# PGA.net
KiCad netlist of a schematic drawn in Altium Designer
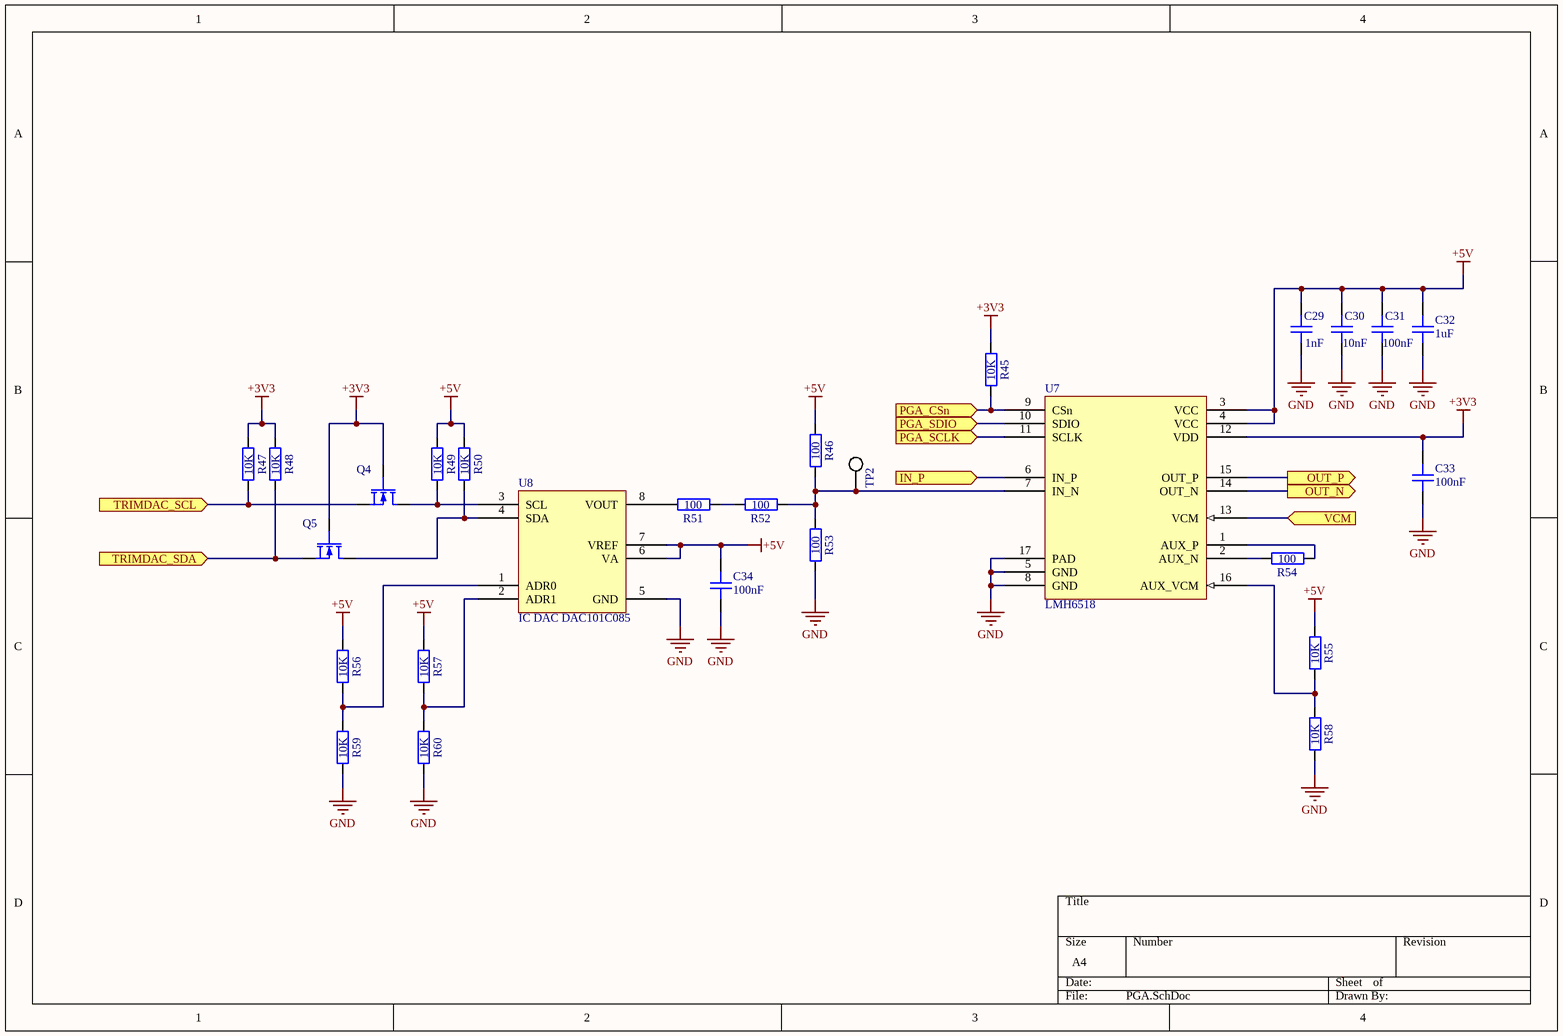
[diagram p0: PGA.SchDoc]

(export (version "E")
  (design (tool "Eeschema 10.0.6"))
  (components
    (comp (ref "C29")
      (value "1nF")
      (footprint "GEN_C_0402")
      (fields (field (name "Comment") "CAP 1nF 50V X7R 0402"))
      (libsource (lib "DSO") (part "CAP 1nF 50V X7R 0402"))
    )
    (comp (ref "C30")
      (value "10nF")
      (footprint "GEN_C_0402")
      (fields (field (name "Comment") "CAP 10nF 50V X7R 0402"))
      (libsource (lib "DSO") (part "CAP 10nF 50V X7R 0402"))
    )
    (comp (ref "C31")
      (value "100nF")
      (footprint "GEN_C_0402")
      (fields (field (name "Comment") "CAP 100nF 16V X7R 0402"))
      (libsource (lib "DSO") (part "CAP 100nF 16V X7R 0402"))
    )
    (comp (ref "C32")
      (value "1uF")
      (footprint "GEN_C_0402")
      (fields (field (name "Comment") "CAP 1uF 25V X5R 0402"))
      (libsource (lib "DSO") (part "CAP 1uF 25V X5R 0402"))
    )
    (comp (ref "C33")
      (value "100nF")
      (footprint "GEN_C_0402")
      (fields (field (name "Comment") "CAP 100nF 16V X7R 0402"))
      (libsource (lib "DSO") (part "CAP 100nF 16V X7R 0402"))
    )
    (comp (ref "C34")
      (value "100nF")
      (footprint "GEN_C_0402")
      (fields (field (name "Comment") "CAP 100nF 16V X7R 0402"))
      (libsource (lib "DSO") (part "CAP 100nF 16V X7R 0402"))
    )
    (comp (ref "Q4")
      (value "NMOS DMN62D0UW")
      (footprint "GEN_SOT_323")
      (libsource (lib "DSO") (part "NMOS DMN62D0UW"))
    )
    (comp (ref "Q5")
      (value "NMOS DMN62D0UW")
      (footprint "GEN_SOT_323")
      (libsource (lib "DSO") (part "NMOS DMN62D0UW"))
    )
    (comp (ref "R45")
      (value "10K")
      (footprint "GEN_R_0402")
      (fields (field (name "TOLERANCE") "1%") (field (name "Comment") "RES 10K OHM 1% 1/10W 0402"))
      (libsource (lib "") (part "RES 10K OHM 1% 1/10W 0402_1"))
    )
    (comp (ref "R46")
      (value "100")
      (footprint "GEN_R_0402")
      (fields (field (name "TOLERANCE") "1%") (field (name "Comment") "RES 100 OHM 1% 1/10W 0402"))
      (libsource (lib "DSO") (part "RES 100 OHM 1% 1/10W 0402"))
    )
    (comp (ref "R47")
      (value "10K")
      (footprint "GEN_R_0402")
      (fields (field (name "TOLERANCE") "1%") (field (name "Comment") "RES 10K OHM 1% 1/10W 0402"))
      (libsource (lib "DSO") (part "RES 10K OHM 1% 1/10W 0402"))
    )
    (comp (ref "R48")
      (value "10K")
      (footprint "GEN_R_0402")
      (fields (field (name "TOLERANCE") "1%") (field (name "Comment") "RES 10K OHM 1% 1/10W 0402"))
      (libsource (lib "DSO") (part "RES 10K OHM 1% 1/10W 0402"))
    )
    (comp (ref "R49")
      (value "10K")
      (footprint "GEN_R_0402")
      (fields (field (name "TOLERANCE") "1%") (field (name "Comment") "RES 10K OHM 1% 1/10W 0402"))
      (libsource (lib "DSO") (part "RES 10K OHM 1% 1/10W 0402"))
    )
    (comp (ref "R50")
      (value "10K")
      (footprint "GEN_R_0402")
      (fields (field (name "TOLERANCE") "1%") (field (name "Comment") "RES 10K OHM 1% 1/10W 0402"))
      (libsource (lib "DSO") (part "RES 10K OHM 1% 1/10W 0402"))
    )
    (comp (ref "R51")
      (value "100")
      (footprint "GEN_R_0402")
      (fields (field (name "TOLERANCE") "1%") (field (name "Comment") "RES 100 OHM 1% 1/10W 0402"))
      (libsource (lib "") (part "RES 100 OHM 1% 1/10W 0402_1"))
    )
    (comp (ref "R52")
      (value "100")
      (footprint "GEN_R_0402")
      (fields (field (name "TOLERANCE") "1%") (field (name "Comment") "RES 100 OHM 1% 1/10W 0402"))
      (libsource (lib "") (part "RES 100 OHM 1% 1/10W 0402_1"))
    )
    (comp (ref "R53")
      (value "100")
      (footprint "GEN_R_0402")
      (fields (field (name "TOLERANCE") "1%") (field (name "Comment") "RES 100 OHM 1% 1/10W 0402"))
      (libsource (lib "DSO") (part "RES 100 OHM 1% 1/10W 0402"))
    )
    (comp (ref "R54")
      (value "100")
      (footprint "GEN_R_0402")
      (fields (field (name "TOLERANCE") "1%") (field (name "Comment") "RES 100 OHM 1% 1/10W 0402"))
      (libsource (lib "") (part "RES 100 OHM 1% 1/10W 0402_1"))
    )
    (comp (ref "R55")
      (value "10K")
      (footprint "GEN_R_0402")
      (fields (field (name "TOLERANCE") "1%") (field (name "Comment") "RES 10K OHM 1% 1/10W 0402"))
      (libsource (lib "") (part "RES 10K OHM 1% 1/10W 0402_1"))
    )
    (comp (ref "R56")
      (value "10K")
      (footprint "GEN_R_0402")
      (fields (field (name "TOLERANCE") "1%") (field (name "Comment") "RES 10K OHM 1% 1/10W 0402"))
      (libsource (lib "DSO") (part "RES 10K OHM 1% 1/10W 0402"))
    )
    (comp (ref "R57")
      (value "10K")
      (footprint "GEN_R_0402")
      (fields (field (name "TOLERANCE") "1%") (field (name "Comment") "RES 10K OHM 1% 1/10W 0402"))
      (libsource (lib "DSO") (part "RES 10K OHM 1% 1/10W 0402"))
    )
    (comp (ref "R58")
      (value "10K")
      (footprint "GEN_R_0402")
      (fields (field (name "TOLERANCE") "1%") (field (name "Comment") "RES 10K OHM 1% 1/10W 0402"))
      (libsource (lib "") (part "RES 10K OHM 1% 1/10W 0402_1"))
    )
    (comp (ref "R59")
      (value "10K")
      (footprint "GEN_R_0402")
      (fields (field (name "TOLERANCE") "1%") (field (name "Comment") "RES 10K OHM 1% 1/10W 0402"))
      (libsource (lib "DSO") (part "RES 10K OHM 1% 1/10W 0402"))
    )
    (comp (ref "R60")
      (value "10K")
      (footprint "GEN_R_0402")
      (fields (field (name "TOLERANCE") "1%") (field (name "Comment") "RES 10K OHM 1% 1/10W 0402"))
      (libsource (lib "DSO") (part "RES 10K OHM 1% 1/10W 0402"))
    )
    (comp (ref "TP2") (value "5019") (footprint "KEY_5019") (libsource (lib "DSO") (part "TP KEYSTONE 5019")))
    (comp (ref "U7")
      (value "LMH6518")
      (footprint "TI_WQFN_RGH0016A")
      (libsource (lib "DSO") (part "IC PGA LMH6518"))
    )
    (comp (ref "U8")
      (value "IC DAC DAC101C085")
      (footprint "TI_VSSOP8_DGK")
      (libsource (lib "DSO") (part "IC DAC DAC101C085"))
    )
  )
  (nets
    (net (code "1") (name "+3V3") (class "Default")
      (node (ref "C33") (pin "2") (pinfunction "2_2") (pintype "passive"))
      (node (ref "Q4") (pin "2") (pinfunction "G_2") (pintype "passive"))
      (node (ref "Q5") (pin "2") (pinfunction "G_2") (pintype "passive"))
      (node (ref "R45") (pin "2") (pinfunction "2_2") (pintype "passive"))
      (node (ref "R47") (pin "2") (pinfunction "2_2") (pintype "passive"))
      (node (ref "R48") (pin "2") (pinfunction "2_2") (pintype "passive"))
      (node (ref "U7") (pin "12") (pinfunction "VDD_12") (pintype "power_in"))
    )
    (net (code "2") (name "+5V") (class "Default")
      (node (ref "C29") (pin "2") (pinfunction "2_2") (pintype "passive"))
      (node (ref "C30") (pin "2") (pinfunction "2_2") (pintype "passive"))
      (node (ref "C31") (pin "2") (pinfunction "2_2") (pintype "passive"))
      (node (ref "C32") (pin "2") (pinfunction "2_2") (pintype "passive"))
      (node (ref "C34") (pin "2") (pinfunction "2_2") (pintype "passive"))
      (node (ref "R46") (pin "2") (pinfunction "2_2") (pintype "passive"))
      (node (ref "R49") (pin "2") (pinfunction "2_2") (pintype "passive"))
      (node (ref "R50") (pin "2") (pinfunction "2_2") (pintype "passive"))
      (node (ref "R55") (pin "2") (pinfunction "2_2") (pintype "passive"))
      (node (ref "R56") (pin "2") (pinfunction "2_2") (pintype "passive"))
      (node (ref "R57") (pin "2") (pinfunction "2_2") (pintype "passive"))
      (node (ref "U7") (pin "3") (pinfunction "VCC_3") (pintype "power_in"))
      (node (ref "U7") (pin "4") (pinfunction "VCC_4") (pintype "power_in"))
      (node (ref "U8") (pin "6") (pinfunction "VA_6") (pintype "power_in"))
      (node (ref "U8") (pin "7") (pinfunction "VREF_7") (pintype "power_in"))
    )
    (net (code "3") (name "/IN_P") (class "Default")
      (node (ref "U7") (pin "6") (pinfunction "IN_P_6") (pintype "passive"))
    )
    (net (code "4") (name "/OUT_N") (class "Default")
      (node (ref "U7") (pin "14") (pinfunction "OUT_N_14") (pintype "passive"))
    )
    (net (code "5") (name "/OUT_P") (class "Default")
      (node (ref "U7") (pin "15") (pinfunction "OUT_P_15") (pintype "passive"))
    )
    (net (code "6") (name "/PGA_CSn") (class "Default")
      (node (ref "R45") (pin "1") (pinfunction "1_1") (pintype "passive"))
      (node (ref "U7") (pin "9") (pinfunction "CSn_9") (pintype "passive"))
    )
    (net (code "7") (name "/PGA_SCLK") (class "Default")
      (node (ref "U7") (pin "11") (pinfunction "SCLK_11") (pintype "passive"))
    )
    (net (code "8") (name "/PGA_SDIO") (class "Default")
      (node (ref "U7") (pin "10") (pinfunction "SDIO_10") (pintype "passive"))
    )
    (net (code "9") (name "/TRIMDAC_SCL") (class "Default")
      (node (ref "Q4") (pin "3") (pinfunction "S_3") (pintype "passive"))
      (node (ref "R47") (pin "1") (pinfunction "1_1") (pintype "passive"))
    )
    (net (code "10") (name "/TRIMDAC_SDA") (class "Default")
      (node (ref "Q5") (pin "3") (pinfunction "S_3") (pintype "passive"))
      (node (ref "R48") (pin "1") (pinfunction "1_1") (pintype "passive"))
    )
    (net (code "11") (name "/VCM") (class "Default")
      (node (ref "U7") (pin "13") (pinfunction "VCM_13") (pintype "input"))
    )
    (net (code "12") (name "GND") (class "Default")
      (node (ref "C29") (pin "1") (pinfunction "1_1") (pintype "passive"))
      (node (ref "C30") (pin "1") (pinfunction "1_1") (pintype "passive"))
      (node (ref "C31") (pin "1") (pinfunction "1_1") (pintype "passive"))
      (node (ref "C32") (pin "1") (pinfunction "1_1") (pintype "passive"))
      (node (ref "C33") (pin "1") (pinfunction "1_1") (pintype "passive"))
      (node (ref "C34") (pin "1") (pinfunction "1_1") (pintype "passive"))
      (node (ref "R53") (pin "1") (pinfunction "1_1") (pintype "passive"))
      (node (ref "R58") (pin "1") (pinfunction "1_1") (pintype "passive"))
      (node (ref "R59") (pin "1") (pinfunction "1_1") (pintype "passive"))
      (node (ref "R60") (pin "1") (pinfunction "1_1") (pintype "passive"))
      (node (ref "U7") (pin "17") (pinfunction "PAD_17") (pintype "power_in"))
      (node (ref "U7") (pin "5") (pinfunction "GND_5") (pintype "power_in"))
      (node (ref "U7") (pin "8") (pinfunction "GND_8") (pintype "power_in"))
      (node (ref "U8") (pin "5") (pinfunction "GND_5") (pintype "power_in"))
    )
    (net (code "13") (name "Net-(Q4-D)") (class "Default")
      (node (ref "Q4") (pin "1") (pinfunction "D_1") (pintype "passive"))
      (node (ref "R49") (pin "1") (pinfunction "1_1") (pintype "passive"))
      (node (ref "U8") (pin "3") (pinfunction "SCL_3") (pintype "passive"))
    )
    (net (code "14") (name "Net-(Q5-D)") (class "Default")
      (node (ref "Q5") (pin "1") (pinfunction "D_1") (pintype "passive"))
      (node (ref "R50") (pin "1") (pinfunction "1_1") (pintype "passive"))
      (node (ref "U8") (pin "4") (pinfunction "SDA_4") (pintype "passive"))
    )
    (net (code "15") (name "Net-(R51-Pad1)") (class "Default")
      (node (ref "R51") (pin "1") (pinfunction "1_1") (pintype "passive"))
      (node (ref "R52") (pin "2") (pinfunction "2_2") (pintype "passive"))
    )
    (net (code "16") (name "Net-(U7-AUX_N)") (class "Default")
      (node (ref "R54") (pin "2") (pinfunction "2_2") (pintype "passive"))
      (node (ref "U7") (pin "2") (pinfunction "AUX_N_2") (pintype "passive"))
    )
    (net (code "17") (name "Net-(U7-AUX_P)") (class "Default")
      (node (ref "R54") (pin "1") (pinfunction "1_1") (pintype "passive"))
      (node (ref "U7") (pin "1") (pinfunction "AUX_P_1") (pintype "passive"))
    )
    (net (code "18") (name "Net-(U7-AUX_VCM)") (class "Default")
      (node (ref "R55") (pin "1") (pinfunction "1_1") (pintype "passive"))
      (node (ref "R58") (pin "2") (pinfunction "2_2") (pintype "passive"))
      (node (ref "U7") (pin "16") (pinfunction "AUX_VCM_16") (pintype "input"))
    )
    (net (code "19") (name "Net-(U7-IN_N)") (class "Default")
      (node (ref "R46") (pin "1") (pinfunction "1_1") (pintype "passive"))
      (node (ref "R52") (pin "1") (pinfunction "1_1") (pintype "passive"))
      (node (ref "R53") (pin "2") (pinfunction "2_2") (pintype "passive"))
      (node (ref "TP2") (pin "1") (pinfunction "1_1") (pintype "passive"))
      (node (ref "U7") (pin "7") (pinfunction "IN_N_7") (pintype "passive"))
    )
    (net (code "20") (name "Net-(U8-ADR0)") (class "Default")
      (node (ref "R56") (pin "1") (pinfunction "1_1") (pintype "passive"))
      (node (ref "R59") (pin "2") (pinfunction "2_2") (pintype "passive"))
      (node (ref "U8") (pin "1") (pinfunction "ADR0_1") (pintype "passive"))
    )
    (net (code "21") (name "Net-(U8-ADR1)") (class "Default")
      (node (ref "R57") (pin "1") (pinfunction "1_1") (pintype "passive"))
      (node (ref "R60") (pin "2") (pinfunction "2_2") (pintype "passive"))
      (node (ref "U8") (pin "2") (pinfunction "ADR1_2") (pintype "passive"))
    )
    (net (code "22") (name "Net-(U8-VOUT)") (class "Default")
      (node (ref "R51") (pin "2") (pinfunction "2_2") (pintype "passive"))
      (node (ref "U8") (pin "8") (pinfunction "VOUT_8") (pintype "passive"))
    )
  )
)
